# F405__mini_2025-11-19.net
KiCad netlist of a schematic drawn in EasyEDA Pro
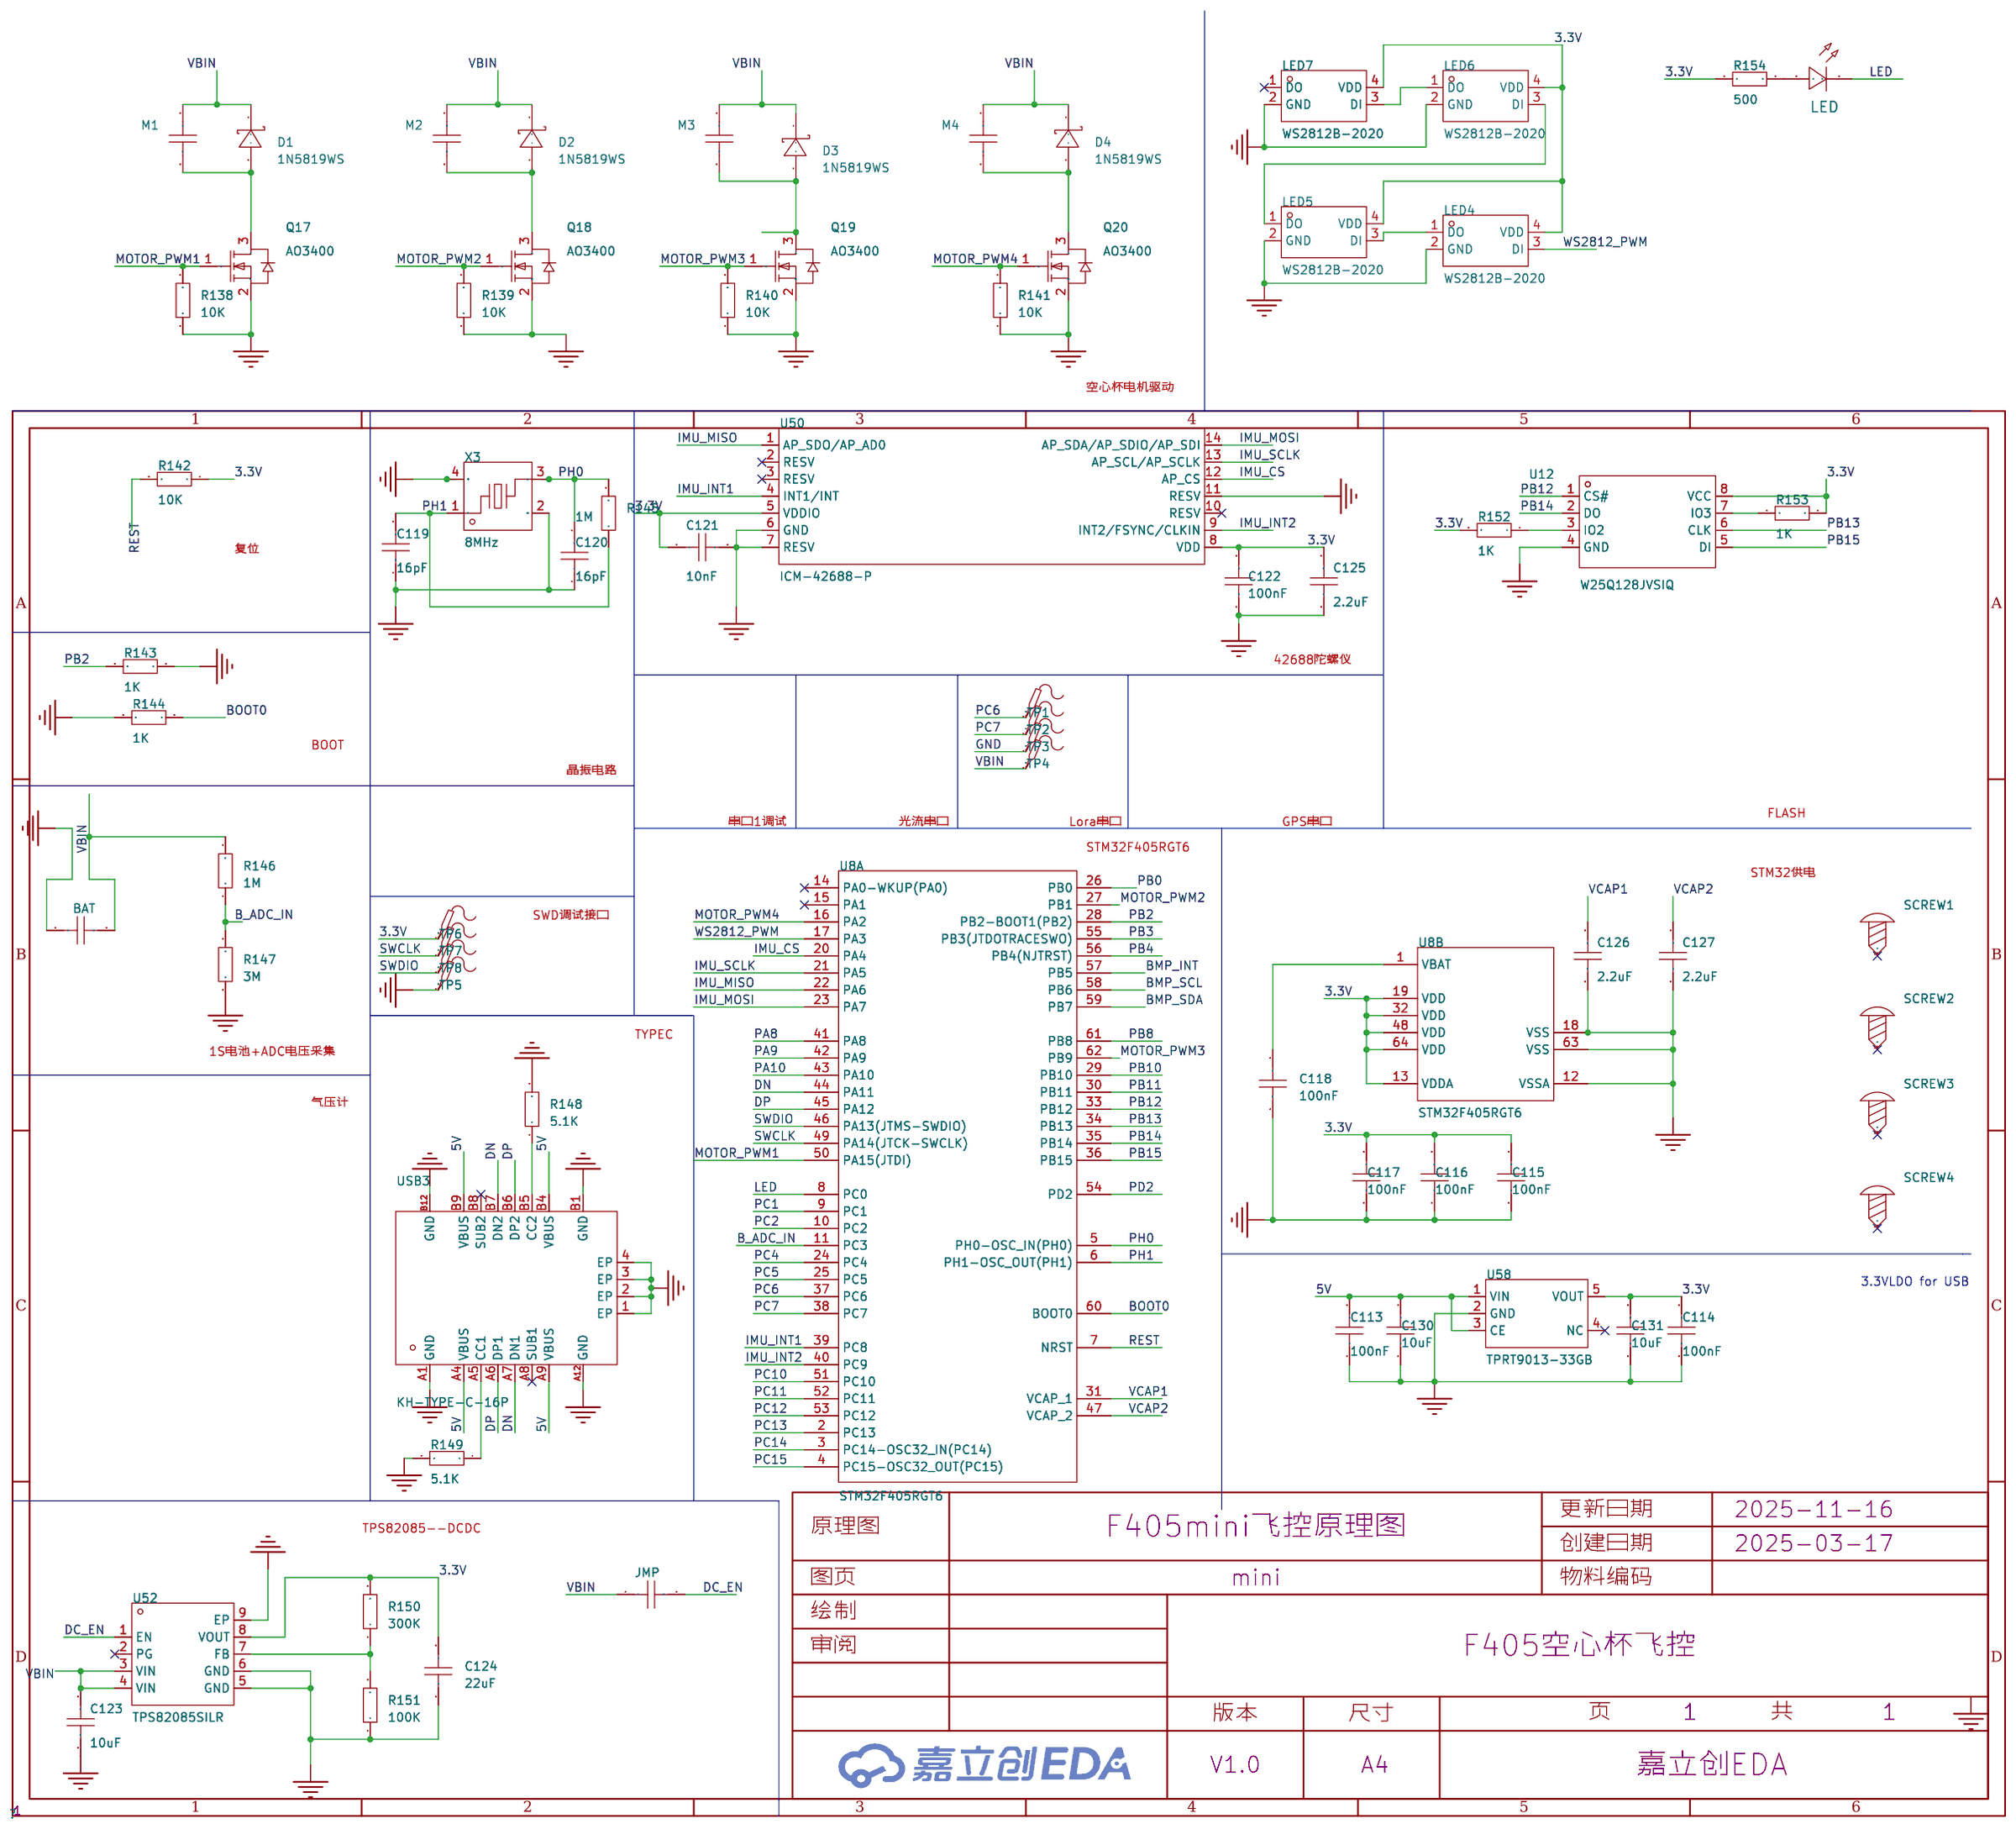
[diagram p0: schematic sheet]

(export (version "E")
  (design (tool "Eeschema 10.0.6"))
  (components
    (comp (ref "BAT")
      (value "3.9nF")
      (footprint "easyedapro:C1812")
      (description "容值:3.9nF;精度:±10%;额定电压:2kV;温度系数:X7R;")
      (fields (field (name "Manufacturer Part") "FV43X392K202EFG") (field (name "Manufacturer") "PSA(信昌电陶)"))
      (libsource (lib "easyedapro") (part "FV43X392K202EFG"))
    )
    (comp (ref "C113")
      (value "100nF")
      (footprint "easyedapro:C1206")
      (libsource (lib "easyedapro") (part "CapAcitance"))
    )
    (comp (ref "C114")
      (value "100nF")
      (footprint "easyedapro:C1206")
      (libsource (lib "easyedapro") (part "CapAcitance"))
    )
    (comp (ref "C115")
      (value "100nF")
      (footprint "easyedapro:C1206")
      (libsource (lib "easyedapro") (part "CapAcitance"))
    )
    (comp (ref "C116")
      (value "100nF")
      (footprint "easyedapro:C1206")
      (libsource (lib "easyedapro") (part "CapAcitance"))
    )
    (comp (ref "C117")
      (value "100nF")
      (footprint "easyedapro:C1206")
      (libsource (lib "easyedapro") (part "CapAcitance"))
    )
    (comp (ref "C118")
      (value "100nF")
      (footprint "easyedapro:C1206")
      (libsource (lib "easyedapro") (part "CapAcitance"))
    )
    (comp (ref "C119")
      (value "16pF")
      (footprint "easyedapro:C1206")
      (libsource (lib "easyedapro") (part "CapAcitance"))
    )
    (comp (ref "C120")
      (value "16pF")
      (footprint "easyedapro:C1206")
      (libsource (lib "easyedapro") (part "CapAcitance"))
    )
    (comp (ref "C121")
      (value "10nF")
      (footprint "easyedapro:C1206")
      (libsource (lib "easyedapro") (part "CapAcitance"))
    )
    (comp (ref "C122")
      (value "100nF")
      (footprint "easyedapro:C1206")
      (libsource (lib "easyedapro") (part "CapAcitance"))
    )
    (comp (ref "C123")
      (value "10uF")
      (footprint "easyedapro:C1206")
      (libsource (lib "easyedapro") (part "CapAcitance"))
    )
    (comp (ref "C124")
      (value "22uF")
      (footprint "easyedapro:C1206")
      (libsource (lib "easyedapro") (part "CapAcitance"))
    )
    (comp (ref "C125")
      (value "2.2uF")
      (footprint "easyedapro:C1206")
      (libsource (lib "easyedapro") (part "CapAcitance"))
    )
    (comp (ref "C126")
      (value "2.2uF")
      (footprint "easyedapro:C1206")
      (libsource (lib "easyedapro") (part "CapAcitance"))
    )
    (comp (ref "C127")
      (value "2.2uF")
      (footprint "easyedapro:C1206")
      (libsource (lib "easyedapro") (part "CapAcitance"))
    )
    (comp (ref "C130")
      (value "10uF")
      (footprint "easyedapro:C1206")
      (libsource (lib "easyedapro") (part "CapAcitance"))
    )
    (comp (ref "C131")
      (value "10uF")
      (footprint "easyedapro:C1206")
      (libsource (lib "easyedapro") (part "CapAcitance"))
    )
    (comp (ref "D1")
      (value "1N5819WS")
      (footprint "easyedapro:SOD-323_L1.8-W1.3-LS2.5-RD")
      (description "正向压降(Vf):600mV@1A;直流反向耐压(Vr):40V;整流电流:1A;")
      (fields (field (name "Manufacturer") "Hottech(合科泰)"))
      (libsource (lib "easyedapro") (part "1N5819WS"))
    )
    (comp (ref "D2")
      (value "1N5819WS")
      (footprint "easyedapro:SOD-323_L1.8-W1.3-LS2.5-RD")
      (description "正向压降(Vf):600mV@1A;直流反向耐压(Vr):40V;整流电流:1A;")
      (fields (field (name "Manufacturer") "Hottech(合科泰)"))
      (libsource (lib "easyedapro") (part "1N5819WS"))
    )
    (comp (ref "D3")
      (value "1N5819WS")
      (footprint "easyedapro:SOD-323_L1.8-W1.3-LS2.5-RD")
      (description "正向压降(Vf):600mV@1A;直流反向耐压(Vr):40V;整流电流:1A;")
      (fields (field (name "Manufacturer") "Hottech(合科泰)"))
      (libsource (lib "easyedapro") (part "1N5819WS"))
    )
    (comp (ref "D4")
      (value "1N5819WS")
      (footprint "easyedapro:SOD-323_L1.8-W1.3-LS2.5-RD")
      (description "正向压降(Vf):600mV@1A;直流反向耐压(Vr):40V;整流电流:1A;")
      (fields (field (name "Manufacturer") "Hottech(合科泰)"))
      (libsource (lib "easyedapro") (part "1N5819WS"))
    )
    (comp (ref "JMP")
      (value "100nF")
      (footprint "easyedapro:C1206")
      (libsource (lib "easyedapro") (part "CapAcitance"))
    )
    (comp (ref "LED")
      (value "~")
      (footprint "easyedapro:LED_0603")
      (libsource (lib "easyedapro") (part "LED_R"))
    )
    (comp (ref "LED4")
      (value "WS2812B-2020")
      (footprint "easyedapro:LED-SMD_4P-L2.0-W2.0-TL_WS2812B-2020")
      (description "12mA，小尺寸，高亮，用于小间距，小尺寸产品（注意防潮，请查阅规格书中对应具体内容）")
      (fields (field (name "Manufacturer") "worldsemi"))
      (libsource (lib "easyedapro") (part "WS2812B-2020"))
    )
    (comp (ref "LED5")
      (value "WS2812B-2020")
      (footprint "easyedapro:LED-SMD_4P-L2.0-W2.0-TL_WS2812B-2020")
      (description "12mA，小尺寸，高亮，用于小间距，小尺寸产品（注意防潮，请查阅规格书中对应具体内容）")
      (fields (field (name "Manufacturer") "worldsemi"))
      (libsource (lib "easyedapro") (part "WS2812B-2020"))
    )
    (comp (ref "LED6")
      (value "WS2812B-2020")
      (footprint "easyedapro:LED-SMD_4P-L2.0-W2.0-TL_WS2812B-2020")
      (description "12mA，小尺寸，高亮，用于小间距，小尺寸产品（注意防潮，请查阅规格书中对应具体内容）")
      (fields (field (name "Manufacturer") "worldsemi"))
      (libsource (lib "easyedapro") (part "WS2812B-2020"))
    )
    (comp (ref "LED7")
      (value "WS2812B-2020")
      (footprint "easyedapro:LED-SMD_4P-L2.0-W2.0-TL_WS2812B-2020")
      (description "12mA，小尺寸，高亮，用于小间距，小尺寸产品（注意防潮，请查阅规格书中对应具体内容）")
      (fields (field (name "Manufacturer") "worldsemi"))
      (libsource (lib "easyedapro") (part "WS2812B-2020"))
    )
    (comp (ref "M1")
      (value "100nF")
      (footprint "easyedapro:C1206")
      (libsource (lib "easyedapro") (part "CapAcitance"))
    )
    (comp (ref "M2")
      (value "100nF")
      (footprint "easyedapro:C1206")
      (libsource (lib "easyedapro") (part "CapAcitance"))
    )
    (comp (ref "M3")
      (value "100nF")
      (footprint "easyedapro:C1206")
      (libsource (lib "easyedapro") (part "CapAcitance"))
    )
    (comp (ref "M4")
      (value "100nF")
      (footprint "easyedapro:C1206")
      (libsource (lib "easyedapro") (part "CapAcitance"))
    )
    (comp (ref "Q17")
      (value "AO3400")
      (footprint "easyedapro:SOT-23_L2.9-W1.3-P1.90-LS2.4-BR")
      (fields (field (name "Manufacturer") "GOODWORK(固得沃克)"))
      (libsource (lib "easyedapro") (part "AO3400_C2938367"))
    )
    (comp (ref "Q18")
      (value "AO3400")
      (footprint "easyedapro:SOT-23_L2.9-W1.3-P1.90-LS2.4-BR")
      (fields (field (name "Manufacturer") "GOODWORK(固得沃克)"))
      (libsource (lib "easyedapro") (part "AO3400_C2938367"))
    )
    (comp (ref "Q19")
      (value "AO3400")
      (footprint "easyedapro:SOT-23_L2.9-W1.3-P1.90-LS2.4-BR")
      (fields (field (name "Manufacturer") "GOODWORK(固得沃克)"))
      (libsource (lib "easyedapro") (part "AO3400_C2938367"))
    )
    (comp (ref "Q20")
      (value "AO3400")
      (footprint "easyedapro:SOT-23_L2.9-W1.3-P1.90-LS2.4-BR")
      (fields (field (name "Manufacturer") "GOODWORK(固得沃克)"))
      (libsource (lib "easyedapro") (part "AO3400_C2938367"))
    )
    (comp (ref "R138")
      (value "10K")
      (footprint "easyedapro:R0402")
      (libsource (lib "easyedapro") (part "电阻"))
    )
    (comp (ref "R139")
      (value "10K")
      (footprint "easyedapro:R0402")
      (libsource (lib "easyedapro") (part "电阻"))
    )
    (comp (ref "R140")
      (value "10K")
      (footprint "easyedapro:R0402")
      (libsource (lib "easyedapro") (part "电阻"))
    )
    (comp (ref "R141")
      (value "10K")
      (footprint "easyedapro:R0402")
      (libsource (lib "easyedapro") (part "电阻"))
    )
    (comp (ref "R142")
      (value "10K")
      (footprint "easyedapro:R0402")
      (libsource (lib "easyedapro") (part "电阻"))
    )
    (comp (ref "R143") (value "1K") (footprint "easyedapro:R0402") (libsource (lib "easyedapro") (part "电阻")))
    (comp (ref "R144") (value "1K") (footprint "easyedapro:R0402") (libsource (lib "easyedapro") (part "电阻")))
    (comp (ref "R145") (value "1M") (footprint "easyedapro:R0402") (libsource (lib "easyedapro") (part "电阻")))
    (comp (ref "R146") (value "1M") (footprint "easyedapro:R0402") (libsource (lib "easyedapro") (part "电阻")))
    (comp (ref "R147") (value "3M") (footprint "easyedapro:R0402") (libsource (lib "easyedapro") (part "电阻")))
    (comp (ref "R148")
      (value "5.1K")
      (footprint "easyedapro:R0402")
      (libsource (lib "easyedapro") (part "电阻"))
    )
    (comp (ref "R149")
      (value "5.1K")
      (footprint "easyedapro:R0402")
      (libsource (lib "easyedapro") (part "电阻"))
    )
    (comp (ref "R150")
      (value "300K")
      (footprint "easyedapro:R0402")
      (libsource (lib "easyedapro") (part "电阻"))
    )
    (comp (ref "R151")
      (value "100K")
      (footprint "easyedapro:R0402")
      (libsource (lib "easyedapro") (part "电阻"))
    )
    (comp (ref "R152") (value "1K") (footprint "easyedapro:R0402") (libsource (lib "easyedapro") (part "电阻")))
    (comp (ref "R153") (value "1K") (footprint "easyedapro:R0402") (libsource (lib "easyedapro") (part "电阻")))
    (comp (ref "R154")
      (value "500")
      (footprint "easyedapro:R0402")
      (libsource (lib "easyedapro") (part "电阻"))
    )
    (comp (ref "SCREW1")
      (value "~")
      (footprint "easyedapro:M2螺丝")
      (libsource (lib "easyedapro") (part "螺丝孔"))
    )
    (comp (ref "SCREW2")
      (value "~")
      (footprint "easyedapro:M2螺丝")
      (libsource (lib "easyedapro") (part "螺丝孔"))
    )
    (comp (ref "SCREW3")
      (value "~")
      (footprint "easyedapro:M2螺丝")
      (libsource (lib "easyedapro") (part "螺丝孔"))
    )
    (comp (ref "SCREW4")
      (value "~")
      (footprint "easyedapro:M2螺丝")
      (libsource (lib "easyedapro") (part "螺丝孔"))
    )
    (comp (ref "TP1")
      (value "~")
      (footprint "easyedapro:Test-Point-0.5mm")
      (description "Test Point 测试点")
      (libsource (lib "easyedapro") (part "Test-Point"))
    )
    (comp (ref "TP2")
      (value "~")
      (footprint "easyedapro:Test-Point-0.5mm")
      (description "Test Point 测试点")
      (libsource (lib "easyedapro") (part "Test-Point"))
    )
    (comp (ref "TP3")
      (value "~")
      (footprint "easyedapro:Test-Point-0.5mm")
      (description "Test Point 测试点")
      (libsource (lib "easyedapro") (part "Test-Point"))
    )
    (comp (ref "TP4")
      (value "~")
      (footprint "easyedapro:Test-Point-0.5mm")
      (description "Test Point 测试点")
      (libsource (lib "easyedapro") (part "Test-Point"))
    )
    (comp (ref "TP5")
      (value "~")
      (footprint "easyedapro:Test-Point-0.5mm")
      (description "Test Point 测试点")
      (libsource (lib "easyedapro") (part "Test-Point"))
    )
    (comp (ref "TP6")
      (value "~")
      (footprint "easyedapro:Test-Point-0.5mm")
      (description "Test Point 测试点")
      (libsource (lib "easyedapro") (part "Test-Point"))
    )
    (comp (ref "TP7")
      (value "~")
      (footprint "easyedapro:Test-Point-0.5mm")
      (description "Test Point 测试点")
      (libsource (lib "easyedapro") (part "Test-Point"))
    )
    (comp (ref "TP8")
      (value "~")
      (footprint "easyedapro:Test-Point-0.5mm")
      (description "Test Point 测试点")
      (libsource (lib "easyedapro") (part "Test-Point"))
    )
    (comp (ref "U8")
      (value "STM32F405RGT6")
      (footprint "easyedapro:LQFP-64_L10.0-W10.0-P0.50-LS12.0-BL")
      (description "CPU内核:ARM-M4;程序存储容量:1MB;RAM总容量:192KB;GPIO端口数量:51;工作电压范围:1.8V~3.6V;CPU最大主频:168MHz;程序存储器类型:FLASH;")
      (fields (field (name "Manufacturer") "ST(意法半导体)"))
      (libsource (lib "easyedapro") (part "STM32F405RGT6"))
    )
    (comp (ref "U12")
      (value "W25Q128JVSIQ")
      (footprint "easyedapro:SOIC-8_L5.3-W5.3-P1.27-LS8.0-BL")
      (description "接口类型:-;存储容量:128Mbit;时钟频率(fc):-;")
      (fields (field (name "Manufacturer") "WINBOND(华邦)"))
      (libsource (lib "easyedapro") (part "w25q128jvsiqtr"))
    )
    (comp (ref "U50")
      (value "ICM-42688-P")
      (footprint "easyedapro:LGA-14_L3.0-W2.5-P0.50-TL")
      (description "传感器类型:加速度计陀螺仪;")
      (fields (field (name "Manufacturer") "TDK InvenSense(应美盛)"))
      (libsource (lib "easyedapro") (part "ICM-42688-P"))
    )
    (comp (ref "U52")
      (value "TPS82085SILR")
      (footprint "easyedapro:USIP-8_L3.0-W2.8-P0.65-BL-EP")
      (description "TPS82085 集成感应器的 3A 降压转换器（截面 &lt; 1.3mm）")
      (fields (field (name "Manufacturer") "TI(德州仪器)"))
      (libsource (lib "easyedapro") (part "TPS82085SILR"))
    )
    (comp (ref "U58")
      (value "TPRT9013-33GB")
      (footprint "easyedapro:SOT-23-5_L3.0-W1.7-P0.95-LS2.8-BL")
      (description "输出类型:固定;工作电压:7V;输出电压:3.3V;输出电流:500mA;电源纹波抑制比(PSRR):70dB@(1kHz);输出极性:正极;")
      (fields (field (name "Manufacturer") "TECH PUBLIC(台舟)"))
      (libsource (lib "easyedapro") (part "TPRT9013-33GB"))
    )
    (comp (ref "USB3")
      (value "KH-TYPE-C-16P")
      (footprint "easyedapro:USB-C-SMD_KH-TYPE-C-16P")
      (description "连接器类型:Type-C;标准:-;公母:母;端口数量:1;触点数量:16P;安装方式:卧贴;额定电流 - 电源:3A;工作温度范围:-40°C~+85°C;")
      (fields (field (name "Manufacturer") "kinghelm(金航标)"))
      (libsource (lib "easyedapro") (part "KH-TYPE-C-16P"))
    )
    (comp (ref "X3")
      (value "8MHz")
      (footprint "easyedapro:CRYSTAL-SMD_4P-L3.2-W2.5-BL")
      (description "晶振类型:贴片晶振;频率:8MHz;常温频差:±10ppm;外接负载电容:20pF;频率稳定度(全温):±20ppm;")
      (fields (field (name "Manufacturer Part") "X32258MSB4SI") (field (name "Manufacturer") "YXC(扬兴晶振)"))
      (libsource (lib "easyedapro") (part "X32258MSB4SI"))
    )
  )
  (nets
    (net (code "1") (name "/3.3V") (class "Default")
      (node (ref "C114") (pin "2") (pinfunction "2_2") (pintype "input"))
      (node (ref "C115") (pin "2") (pinfunction "2_2") (pintype "input"))
      (node (ref "C116") (pin "2") (pinfunction "2_2") (pintype "input"))
      (node (ref "C117") (pin "2") (pinfunction "2_2") (pintype "input"))
      (node (ref "C121") (pin "1") (pinfunction "1_1") (pintype "input"))
      (node (ref "C122") (pin "2") (pinfunction "2_2") (pintype "input"))
      (node (ref "C124") (pin "2") (pinfunction "2_2") (pintype "input"))
      (node (ref "C125") (pin "2") (pinfunction "2_2") (pintype "input"))
      (node (ref "C131") (pin "2") (pinfunction "2_2") (pintype "input"))
      (node (ref "LED4") (pin "4") (pinfunction "VDD_4") (pintype "unspecified"))
      (node (ref "LED5") (pin "4") (pinfunction "VDD_4") (pintype "unspecified"))
      (node (ref "LED6") (pin "4") (pinfunction "VDD_4") (pintype "unspecified"))
      (node (ref "LED7") (pin "4") (pinfunction "VDD_4") (pintype "unspecified"))
      (node (ref "R142") (pin "1") (pinfunction "1_1") (pintype "input"))
      (node (ref "R150") (pin "2") (pinfunction "2_2") (pintype "input"))
      (node (ref "R152") (pin "2") (pinfunction "2_2") (pintype "input"))
      (node (ref "R153") (pin "1") (pinfunction "1_1") (pintype "input"))
      (node (ref "R154") (pin "1") (pinfunction "1_1") (pintype "input"))
      (node (ref "TP6") (pin "1") (pinfunction "1_1") (pintype "input"))
      (node (ref "U12") (pin "8") (pinfunction "VCC_8") (pintype "unspecified"))
      (node (ref "U50") (pin "5") (pinfunction "VDDIO_5") (pintype "unspecified"))
      (node (ref "U50") (pin "8") (pinfunction "VDD_8") (pintype "unspecified"))
      (node (ref "U52") (pin "8") (pinfunction "VOUT_8") (pintype "unspecified"))
      (node (ref "U58") (pin "5") (pinfunction "VOUT_5") (pintype "unspecified"))
      (node (ref "U8") (pin "13") (pinfunction "VDDA_13") (pintype "unspecified"))
      (node (ref "U8") (pin "19") (pinfunction "VDD_19") (pintype "unspecified"))
      (node (ref "U8") (pin "32") (pinfunction "VDD_32") (pintype "unspecified"))
      (node (ref "U8") (pin "48") (pinfunction "VDD_48") (pintype "unspecified"))
      (node (ref "U8") (pin "64") (pinfunction "VDD_64") (pintype "unspecified"))
    )
    (net (code "2") (name "/5V") (class "Default")
      (node (ref "C113") (pin "2") (pinfunction "2_2") (pintype "input"))
      (node (ref "C130") (pin "2") (pinfunction "2_2") (pintype "input"))
      (node (ref "U58") (pin "1") (pinfunction "VIN_1") (pintype "unspecified"))
      (node (ref "U58") (pin "3") (pinfunction "CE_3") (pintype "unspecified"))
      (node (ref "USB3") (pin "A4") (pinfunction "VBUS_A4") (pintype "unspecified"))
      (node (ref "USB3") (pin "A9") (pinfunction "VBUS_A9") (pintype "unspecified"))
      (node (ref "USB3") (pin "B4") (pinfunction "VBUS_B4") (pintype "unspecified"))
      (node (ref "USB3") (pin "B9") (pinfunction "VBUS_B9") (pintype "unspecified"))
    )
    (net (code "3") (name "/BMP_INT") (class "Default")
      (node (ref "U8") (pin "57") (pinfunction "PB5_57") (pintype "bidirectional"))
    )
    (net (code "4") (name "/BMP_SCL") (class "Default")
      (node (ref "U8") (pin "58") (pinfunction "PB6_58") (pintype "bidirectional"))
    )
    (net (code "5") (name "/BMP_SDA") (class "Default")
      (node (ref "U8") (pin "59") (pinfunction "PB7_59") (pintype "bidirectional"))
    )
    (net (code "6") (name "/BOOT0") (class "Default")
      (node (ref "R144") (pin "1") (pinfunction "1_1") (pintype "input"))
      (node (ref "U8") (pin "60") (pinfunction "BOOT0_60") (pintype "unspecified"))
    )
    (net (code "7") (name "/B_ADC_IN") (class "Default")
      (node (ref "R146") (pin "1") (pinfunction "1_1") (pintype "input"))
      (node (ref "R147") (pin "2") (pinfunction "2_2") (pintype "input"))
      (node (ref "U8") (pin "11") (pinfunction "PC3_11") (pintype "bidirectional"))
    )
    (net (code "8") (name "/DC_EN") (class "Default")
      (node (ref "JMP") (pin "2") (pinfunction "2_2") (pintype "input"))
      (node (ref "U52") (pin "1") (pinfunction "EN_1") (pintype "unspecified"))
    )
    (net (code "9") (name "/DN") (class "Default")
      (node (ref "U8") (pin "44") (pinfunction "PA11_44") (pintype "bidirectional"))
      (node (ref "USB3") (pin "A7") (pinfunction "DN1_A7") (pintype "unspecified"))
      (node (ref "USB3") (pin "B7") (pinfunction "DN2_B7") (pintype "unspecified"))
    )
    (net (code "10") (name "/DP") (class "Default")
      (node (ref "U8") (pin "45") (pinfunction "PA12_45") (pintype "bidirectional"))
      (node (ref "USB3") (pin "A6") (pinfunction "DP1_A6") (pintype "unspecified"))
      (node (ref "USB3") (pin "B6") (pinfunction "DP2_B6") (pintype "unspecified"))
    )
    (net (code "11") (name "/IMU_CS") (class "Default")
      (node (ref "U50") (pin "12") (pinfunction "AP_CS_12") (pintype "unspecified"))
      (node (ref "U8") (pin "20") (pinfunction "PA4_20") (pintype "bidirectional"))
    )
    (net (code "12") (name "/IMU_INT1") (class "Default")
      (node (ref "U50") (pin "4") (pinfunction "INT1/INT_4") (pintype "unspecified"))
      (node (ref "U8") (pin "39") (pinfunction "PC8_39") (pintype "bidirectional"))
    )
    (net (code "13") (name "/IMU_INT2") (class "Default")
      (node (ref "U50") (pin "9") (pinfunction "INT2/FSYNC/CLKIN_9") (pintype "unspecified"))
      (node (ref "U8") (pin "40") (pinfunction "PC9_40") (pintype "bidirectional"))
    )
    (net (code "14") (name "/IMU_MISO") (class "Default")
      (node (ref "U50") (pin "1") (pinfunction "AP_SDO/AP_AD0_1") (pintype "unspecified"))
      (node (ref "U8") (pin "22") (pinfunction "PA6_22") (pintype "bidirectional"))
    )
    (net (code "15") (name "/IMU_MOSI") (class "Default")
      (node (ref "U50") (pin "14") (pinfunction "AP_SDA/AP_SDIO/AP_SDI_14") (pintype "unspecified"))
      (node (ref "U8") (pin "23") (pinfunction "PA7_23") (pintype "bidirectional"))
    )
    (net (code "16") (name "/IMU_SCLK") (class "Default")
      (node (ref "U50") (pin "13") (pinfunction "AP_SCL/AP_SCLK_13") (pintype "unspecified"))
      (node (ref "U8") (pin "21") (pinfunction "PA5_21") (pintype "bidirectional"))
    )
    (net (code "17") (name "/LED") (class "Default")
      (node (ref "LED") (pin "1") (pinfunction "C_1") (pintype "input"))
      (node (ref "U8") (pin "8") (pinfunction "PC0_8") (pintype "bidirectional"))
    )
    (net (code "18") (name "/MOTOR_PWM1") (class "Default")
      (node (ref "Q17") (pin "1") (pinfunction "G_1") (pintype "unspecified"))
      (node (ref "R138") (pin "2") (pinfunction "2_2") (pintype "input"))
      (node (ref "U8") (pin "50") (pinfunction "PA15(JTDI)_50") (pintype "bidirectional"))
    )
    (net (code "19") (name "/MOTOR_PWM2") (class "Default")
      (node (ref "Q18") (pin "1") (pinfunction "G_1") (pintype "unspecified"))
      (node (ref "R139") (pin "2") (pinfunction "2_2") (pintype "input"))
      (node (ref "U8") (pin "27") (pinfunction "PB1_27") (pintype "bidirectional"))
    )
    (net (code "20") (name "/MOTOR_PWM3") (class "Default")
      (node (ref "Q19") (pin "1") (pinfunction "G_1") (pintype "unspecified"))
      (node (ref "R140") (pin "2") (pinfunction "2_2") (pintype "input"))
      (node (ref "U8") (pin "62") (pinfunction "PB9_62") (pintype "bidirectional"))
    )
    (net (code "21") (name "/MOTOR_PWM4") (class "Default")
      (node (ref "Q20") (pin "1") (pinfunction "G_1") (pintype "unspecified"))
      (node (ref "R141") (pin "2") (pinfunction "2_2") (pintype "input"))
      (node (ref "U8") (pin "16") (pinfunction "PA2_16") (pintype "bidirectional"))
    )
    (net (code "22") (name "/PA8") (class "Default")
      (node (ref "U8") (pin "41") (pinfunction "PA8_41") (pintype "bidirectional"))
    )
    (net (code "23") (name "/PA9") (class "Default")
      (node (ref "U8") (pin "42") (pinfunction "PA9_42") (pintype "bidirectional"))
    )
    (net (code "24") (name "/PA10") (class "Default")
      (node (ref "U8") (pin "43") (pinfunction "PA10_43") (pintype "bidirectional"))
    )
    (net (code "25") (name "/PB0") (class "Default")
      (node (ref "U8") (pin "26") (pinfunction "PB0_26") (pintype "bidirectional"))
    )
    (net (code "26") (name "/PB2") (class "Default")
      (node (ref "R143") (pin "2") (pinfunction "2_2") (pintype "input"))
      (node (ref "U8") (pin "28") (pinfunction "PB2-BOOT1(PB2)_28") (pintype "bidirectional"))
    )
    (net (code "27") (name "/PB3") (class "Default")
      (node (ref "U8") (pin "55") (pinfunction "PB3(JTDOTRACESWO)_55") (pintype "bidirectional"))
    )
    (net (code "28") (name "/PB4") (class "Default")
      (node (ref "U8") (pin "56") (pinfunction "PB4(NJTRST)_56") (pintype "bidirectional"))
    )
    (net (code "29") (name "/PB8") (class "Default")
      (node (ref "U8") (pin "61") (pinfunction "PB8_61") (pintype "bidirectional"))
    )
    (net (code "30") (name "/PB10") (class "Default")
      (node (ref "U8") (pin "29") (pinfunction "PB10_29") (pintype "bidirectional"))
    )
    (net (code "31") (name "/PB11") (class "Default")
      (node (ref "U8") (pin "30") (pinfunction "PB11_30") (pintype "bidirectional"))
    )
    (net (code "32") (name "/PB12") (class "Default")
      (node (ref "U12") (pin "1") (pinfunction "CS#_1") (pintype "unspecified"))
      (node (ref "U8") (pin "33") (pinfunction "PB12_33") (pintype "bidirectional"))
    )
    (net (code "33") (name "/PB13") (class "Default")
      (node (ref "U12") (pin "6") (pinfunction "CLK_6") (pintype "unspecified"))
      (node (ref "U8") (pin "34") (pinfunction "PB13_34") (pintype "bidirectional"))
    )
    (net (code "34") (name "/PB14") (class "Default")
      (node (ref "U12") (pin "2") (pinfunction "DO_2") (pintype "unspecified"))
      (node (ref "U8") (pin "35") (pinfunction "PB14_35") (pintype "bidirectional"))
    )
    (net (code "35") (name "/PB15") (class "Default")
      (node (ref "U12") (pin "5") (pinfunction "DI_5") (pintype "unspecified"))
      (node (ref "U8") (pin "36") (pinfunction "PB15_36") (pintype "bidirectional"))
    )
    (net (code "36") (name "/PC1") (class "Default")
      (node (ref "U8") (pin "9") (pinfunction "PC1_9") (pintype "bidirectional"))
    )
    (net (code "37") (name "/PC2") (class "Default")
      (node (ref "U8") (pin "10") (pinfunction "PC2_10") (pintype "bidirectional"))
    )
    (net (code "38") (name "/PC4") (class "Default")
      (node (ref "U8") (pin "24") (pinfunction "PC4_24") (pintype "bidirectional"))
    )
    (net (code "39") (name "/PC5") (class "Default")
      (node (ref "U8") (pin "25") (pinfunction "PC5_25") (pintype "bidirectional"))
    )
    (net (code "40") (name "/PC6") (class "Default")
      (node (ref "TP1") (pin "1") (pinfunction "1_1") (pintype "input"))
      (node (ref "U8") (pin "37") (pinfunction "PC6_37") (pintype "bidirectional"))
    )
    (net (code "41") (name "/PC7") (class "Default")
      (node (ref "TP2") (pin "1") (pinfunction "1_1") (pintype "input"))
      (node (ref "U8") (pin "38") (pinfunction "PC7_38") (pintype "bidirectional"))
    )
    (net (code "42") (name "/PC10") (class "Default")
      (node (ref "U8") (pin "51") (pinfunction "PC10_51") (pintype "bidirectional"))
    )
    (net (code "43") (name "/PC11") (class "Default")
      (node (ref "U8") (pin "52") (pinfunction "PC11_52") (pintype "bidirectional"))
    )
    (net (code "44") (name "/PC12") (class "Default")
      (node (ref "U8") (pin "53") (pinfunction "PC12_53") (pintype "bidirectional"))
    )
    (net (code "45") (name "/PC13") (class "Default")
      (node (ref "U8") (pin "2") (pinfunction "PC13_2") (pintype "bidirectional"))
    )
    (net (code "46") (name "/PC14") (class "Default")
      (node (ref "U8") (pin "3") (pinfunction "PC14-OSC32_IN(PC14)_3") (pintype "bidirectional"))
    )
    (net (code "47") (name "/PC15") (class "Default")
      (node (ref "U8") (pin "4") (pinfunction "PC15-OSC32_OUT(PC15)_4") (pintype "bidirectional"))
    )
    (net (code "48") (name "/PD2") (class "Default")
      (node (ref "U8") (pin "54") (pinfunction "PD2_54") (pintype "bidirectional"))
    )
    (net (code "49") (name "/PH0") (class "Default")
      (node (ref "C120") (pin "2") (pinfunction "2_2") (pintype "input"))
      (node (ref "R145") (pin "2") (pinfunction "2_2") (pintype "input"))
      (node (ref "U8") (pin "5") (pinfunction "PH0-OSC_IN(PH0)_5") (pintype "bidirectional"))
      (node (ref "X3") (pin "3") (pinfunction "3_3") (pintype "input"))
    )
    (net (code "50") (name "/PH1") (class "Default")
      (node (ref "C119") (pin "2") (pinfunction "2_2") (pintype "input"))
      (node (ref "R145") (pin "1") (pinfunction "1_1") (pintype "input"))
      (node (ref "U8") (pin "6") (pinfunction "PH1-OSC_OUT(PH1)_6") (pintype "bidirectional"))
      (node (ref "X3") (pin "1") (pinfunction "1_1") (pintype "input"))
    )
    (net (code "51") (name "/REST") (class "Default")
      (node (ref "R142") (pin "2") (pinfunction "2_2") (pintype "input"))
      (node (ref "U8") (pin "7") (pinfunction "NRST_7") (pintype "bidirectional"))
    )
    (net (code "52") (name "/SWCLK") (class "Default")
      (node (ref "TP7") (pin "1") (pinfunction "1_1") (pintype "input"))
      (node (ref "U8") (pin "49") (pinfunction "PA14(JTCK-SWCLK)_49") (pintype "bidirectional"))
    )
    (net (code "53") (name "/SWDIO") (class "Default")
      (node (ref "TP8") (pin "1") (pinfunction "1_1") (pintype "input"))
      (node (ref "U8") (pin "46") (pinfunction "PA13(JTMS-SWDIO)_46") (pintype "bidirectional"))
    )
    (net (code "54") (name "/VBIN") (class "Default")
      (node (ref "BAT") (pin "2") (pinfunction "2_2") (pintype "unspecified"))
      (node (ref "C123") (pin "2") (pinfunction "2_2") (pintype "input"))
      (node (ref "D1") (pin "1") (pinfunction "K_1") (pintype "unspecified"))
      (node (ref "D2") (pin "1") (pinfunction "K_1") (pintype "unspecified"))
      (node (ref "D3") (pin "1") (pinfunction "K_1") (pintype "unspecified"))
      (node (ref "D4") (pin "1") (pinfunction "K_1") (pintype "unspecified"))
      (node (ref "JMP") (pin "1") (pinfunction "1_1") (pintype "input"))
      (node (ref "M1") (pin "1") (pinfunction "1_1") (pintype "input"))
      (node (ref "M2") (pin "1") (pinfunction "1_1") (pintype "input"))
      (node (ref "M3") (pin "1") (pinfunction "1_1") (pintype "input"))
      (node (ref "M4") (pin "1") (pinfunction "1_1") (pintype "input"))
      (node (ref "R146") (pin "2") (pinfunction "2_2") (pintype "input"))
      (node (ref "TP4") (pin "1") (pinfunction "1_1") (pintype "input"))
      (node (ref "U52") (pin "3") (pinfunction "VIN_3") (pintype "unspecified"))
      (node (ref "U52") (pin "4") (pinfunction "VIN_4") (pintype "unspecified"))
    )
    (net (code "55") (name "/VCAP1") (class "Default")
      (node (ref "C126") (pin "2") (pinfunction "2_2") (pintype "input"))
      (node (ref "U8") (pin "31") (pinfunction "VCAP_1_31") (pintype "unspecified"))
    )
    (net (code "56") (name "/VCAP2") (class "Default")
      (node (ref "C127") (pin "2") (pinfunction "2_2") (pintype "input"))
      (node (ref "U8") (pin "47") (pinfunction "VCAP_2_47") (pintype "unspecified"))
    )
    (net (code "57") (name "/WS2812_PWM") (class "Default")
      (node (ref "LED4") (pin "3") (pinfunction "DI_3") (pintype "unspecified"))
      (node (ref "U8") (pin "17") (pinfunction "PA3_17") (pintype "bidirectional"))
    )
    (net (code "58") (name "GND") (class "Default")
      (node (ref "BAT") (pin "1") (pinfunction "1_1") (pintype "unspecified"))
      (node (ref "C113") (pin "1") (pinfunction "1_1") (pintype "input"))
      (node (ref "C114") (pin "1") (pinfunction "1_1") (pintype "input"))
      (node (ref "C115") (pin "1") (pinfunction "1_1") (pintype "input"))
      (node (ref "C116") (pin "1") (pinfunction "1_1") (pintype "input"))
      (node (ref "C117") (pin "1") (pinfunction "1_1") (pintype "input"))
      (node (ref "C118") (pin "1") (pinfunction "1_1") (pintype "input"))
      (node (ref "C119") (pin "1") (pinfunction "1_1") (pintype "input"))
      (node (ref "C120") (pin "1") (pinfunction "1_1") (pintype "input"))
      (node (ref "C121") (pin "2") (pinfunction "2_2") (pintype "input"))
      (node (ref "C122") (pin "1") (pinfunction "1_1") (pintype "input"))
      (node (ref "C123") (pin "1") (pinfunction "1_1") (pintype "input"))
      (node (ref "C124") (pin "1") (pinfunction "1_1") (pintype "input"))
      (node (ref "C125") (pin "1") (pinfunction "1_1") (pintype "input"))
      (node (ref "C126") (pin "1") (pinfunction "1_1") (pintype "input"))
      (node (ref "C127") (pin "1") (pinfunction "1_1") (pintype "input"))
      (node (ref "C130") (pin "1") (pinfunction "1_1") (pintype "input"))
      (node (ref "C131") (pin "1") (pinfunction "1_1") (pintype "input"))
      (node (ref "LED4") (pin "2") (pinfunction "GND_2") (pintype "unspecified"))
      (node (ref "LED5") (pin "2") (pinfunction "GND_2") (pintype "unspecified"))
      (node (ref "LED6") (pin "2") (pinfunction "GND_2") (pintype "unspecified"))
      (node (ref "LED7") (pin "2") (pinfunction "GND_2") (pintype "unspecified"))
      (node (ref "Q17") (pin "2") (pinfunction "S_2") (pintype "unspecified"))
      (node (ref "Q18") (pin "2") (pinfunction "S_2") (pintype "unspecified"))
      (node (ref "Q19") (pin "2") (pinfunction "S_2") (pintype "unspecified"))
      (node (ref "Q20") (pin "2") (pinfunction "S_2") (pintype "unspecified"))
      (node (ref "R138") (pin "1") (pinfunction "1_1") (pintype "input"))
      (node (ref "R139") (pin "1") (pinfunction "1_1") (pintype "input"))
      (node (ref "R140") (pin "1") (pinfunction "1_1") (pintype "input"))
      (node (ref "R141") (pin "1") (pinfunction "1_1") (pintype "input"))
      (node (ref "R143") (pin "1") (pinfunction "1_1") (pintype "input"))
      (node (ref "R144") (pin "2") (pinfunction "2_2") (pintype "input"))
      (node (ref "R147") (pin "1") (pinfunction "1_1") (pintype "input"))
      (node (ref "R148") (pin "2") (pinfunction "2_2") (pintype "input"))
      (node (ref "R149") (pin "2") (pinfunction "2_2") (pintype "input"))
      (node (ref "R151") (pin "1") (pinfunction "1_1") (pintype "input"))
      (node (ref "TP3") (pin "1") (pinfunction "1_1") (pintype "input"))
      (node (ref "TP5") (pin "1") (pinfunction "1_1") (pintype "input"))
      (node (ref "U12") (pin "4") (pinfunction "GND_4") (pintype "unspecified"))
      (node (ref "U50") (pin "11") (pinfunction "RESV_11") (pintype "unspecified"))
      (node (ref "U50") (pin "6") (pinfunction "GND_6") (pintype "unspecified"))
      (node (ref "U50") (pin "7") (pinfunction "RESV_7") (pintype "unspecified"))
      (node (ref "U52") (pin "5") (pinfunction "GND_5") (pintype "unspecified"))
      (node (ref "U52") (pin "6") (pinfunction "GND_6") (pintype "unspecified"))
      (node (ref "U52") (pin "9") (pinfunction "EP_9") (pintype "unspecified"))
      (node (ref "U58") (pin "2") (pinfunction "GND_2") (pintype "unspecified"))
      (node (ref "U8") (pin "12") (pinfunction "VSSA_12") (pintype "unspecified"))
      (node (ref "U8") (pin "18") (pinfunction "VSS_18") (pintype "unspecified"))
      (node (ref "U8") (pin "63") (pinfunction "VSS_63") (pintype "unspecified"))
      (node (ref "USB3") (pin "1") (pinfunction "EP_1") (pintype "unspecified"))
      (node (ref "USB3") (pin "2") (pinfunction "EP_2") (pintype "unspecified"))
      (node (ref "USB3") (pin "3") (pinfunction "EP_3") (pintype "unspecified"))
      (node (ref "USB3") (pin "4") (pinfunction "EP_4") (pintype "unspecified"))
      (node (ref "USB3") (pin "A1") (pinfunction "GND_A1") (pintype "unspecified"))
      (node (ref "USB3") (pin "A12") (pinfunction "GND_A12") (pintype "unspecified"))
      (node (ref "USB3") (pin "B1") (pinfunction "GND_B1") (pintype "unspecified"))
      (node (ref "USB3") (pin "B12") (pinfunction "GND_B12") (pintype "unspecified"))
      (node (ref "X3") (pin "2") (pinfunction "GND_2") (pintype "input"))
      (node (ref "X3") (pin "4") (pinfunction "GND_4") (pintype "input"))
    )
    (net (code "59") (name "Net-(D1-A)") (class "Default")
      (node (ref "D1") (pin "2") (pinfunction "A_2") (pintype "unspecified"))
      (node (ref "M1") (pin "2") (pinfunction "2_2") (pintype "input"))
      (node (ref "Q17") (pin "3") (pinfunction "D_3") (pintype "unspecified"))
    )
    (net (code "60") (name "Net-(D2-A)") (class "Default")
      (node (ref "D2") (pin "2") (pinfunction "A_2") (pintype "unspecified"))
      (node (ref "M2") (pin "2") (pinfunction "2_2") (pintype "input"))
      (node (ref "Q18") (pin "3") (pinfunction "D_3") (pintype "unspecified"))
    )
    (net (code "61") (name "Net-(D3-A)") (class "Default")
      (node (ref "D3") (pin "2") (pinfunction "A_2") (pintype "unspecified"))
      (node (ref "M3") (pin "2") (pinfunction "2_2") (pintype "input"))
      (node (ref "Q19") (pin "3") (pinfunction "D_3") (pintype "unspecified"))
    )
    (net (code "62") (name "Net-(D4-A)") (class "Default")
      (node (ref "D4") (pin "2") (pinfunction "A_2") (pintype "unspecified"))
      (node (ref "M4") (pin "2") (pinfunction "2_2") (pintype "input"))
      (node (ref "Q20") (pin "3") (pinfunction "D_3") (pintype "unspecified"))
    )
    (net (code "63") (name "Net-(LED-A)") (class "Default")
      (node (ref "LED") (pin "2") (pinfunction "A_2") (pintype "input"))
      (node (ref "R154") (pin "2") (pinfunction "2_2") (pintype "input"))
    )
    (net (code "64") (name "Net-(LED4-DO)") (class "Default")
      (node (ref "LED4") (pin "1") (pinfunction "DO_1") (pintype "unspecified"))
      (node (ref "LED5") (pin "3") (pinfunction "DI_3") (pintype "unspecified"))
    )
    (net (code "65") (name "Net-(LED5-DO)") (class "Default")
      (node (ref "LED5") (pin "1") (pinfunction "DO_1") (pintype "unspecified"))
      (node (ref "LED6") (pin "3") (pinfunction "DI_3") (pintype "unspecified"))
    )
    (net (code "66") (name "Net-(LED6-DO)") (class "Default")
      (node (ref "LED6") (pin "1") (pinfunction "DO_1") (pintype "unspecified"))
      (node (ref "LED7") (pin "3") (pinfunction "DI_3") (pintype "unspecified"))
    )
    (net (code "67") (name "Net-(U8B-VBAT)") (class "Default")
      (node (ref "C118") (pin "2") (pinfunction "2_2") (pintype "input"))
      (node (ref "U8") (pin "1") (pinfunction "VBAT_1") (pintype "unspecified"))
    )
    (net (code "68") (name "Net-(U12-IO2)") (class "Default")
      (node (ref "R152") (pin "1") (pinfunction "1_1") (pintype "input"))
      (node (ref "U12") (pin "3") (pinfunction "IO2_3") (pintype "unspecified"))
    )
    (net (code "69") (name "Net-(U12-IO3)") (class "Default")
      (node (ref "R153") (pin "2") (pinfunction "2_2") (pintype "input"))
      (node (ref "U12") (pin "7") (pinfunction "IO3_7") (pintype "unspecified"))
    )
    (net (code "70") (name "Net-(U52-FB)") (class "Default")
      (node (ref "R150") (pin "1") (pinfunction "1_1") (pintype "input"))
      (node (ref "R151") (pin "2") (pinfunction "2_2") (pintype "input"))
      (node (ref "U52") (pin "7") (pinfunction "FB_7") (pintype "unspecified"))
    )
    (net (code "71") (name "Net-(USB3-CC1)") (class "Default")
      (node (ref "R149") (pin "1") (pinfunction "1_1") (pintype "input"))
      (node (ref "USB3") (pin "A5") (pinfunction "CC1_A5") (pintype "unspecified"))
    )
    (net (code "72") (name "Net-(USB3-CC2)") (class "Default")
      (node (ref "R148") (pin "1") (pinfunction "1_1") (pintype "input"))
      (node (ref "USB3") (pin "B5") (pinfunction "CC2_B5") (pintype "unspecified"))
    )
    (net (code "73") (name "unconnected-(LED7-DO-Pad1)") (class "Default")
      (node (ref "LED7") (pin "1") (pinfunction "DO_1") (pintype "unspecified+no_connect"))
    )
    (net (code "74") (name "unconnected-(SCREW1-Pad1)") (class "Default")
      (node (ref "SCREW1") (pin "1") (pinfunction "1_1") (pintype "input+no_connect"))
    )
    (net (code "75") (name "unconnected-(SCREW2-Pad1)") (class "Default")
      (node (ref "SCREW2") (pin "1") (pinfunction "1_1") (pintype "input+no_connect"))
    )
    (net (code "76") (name "unconnected-(SCREW3-Pad1)") (class "Default")
      (node (ref "SCREW3") (pin "1") (pinfunction "1_1") (pintype "input+no_connect"))
    )
    (net (code "77") (name "unconnected-(SCREW4-Pad1)") (class "Default")
      (node (ref "SCREW4") (pin "1") (pinfunction "1_1") (pintype "input+no_connect"))
    )
    (net (code "78") (name "unconnected-(U8A-PA0-WKUP(PA0)-Pad14)") (class "Default")
      (node (ref "U8") (pin "14") (pinfunction "PA0-WKUP(PA0)_14") (pintype "bidirectional+no_connect"))
    )
    (net (code "79") (name "unconnected-(U8A-PA1-Pad15)") (class "Default")
      (node (ref "U8") (pin "15") (pinfunction "PA1_15") (pintype "bidirectional+no_connect"))
    )
    (net (code "80") (name "unconnected-(U50-RESV-Pad2)") (class "Default")
      (node (ref "U50") (pin "2") (pinfunction "RESV_2") (pintype "unspecified+no_connect"))
    )
    (net (code "81") (name "unconnected-(U50-RESV-Pad3)") (class "Default")
      (node (ref "U50") (pin "3") (pinfunction "RESV_3") (pintype "unspecified+no_connect"))
    )
    (net (code "82") (name "unconnected-(U50-RESV-Pad10)") (class "Default")
      (node (ref "U50") (pin "10") (pinfunction "RESV_10") (pintype "unspecified+no_connect"))
    )
    (net (code "83") (name "unconnected-(U52-PG-Pad2)") (class "Default")
      (node (ref "U52") (pin "2") (pinfunction "PG_2") (pintype "unspecified+no_connect"))
    )
    (net (code "84") (name "unconnected-(U58-NC-Pad4)") (class "Default")
      (node (ref "U58") (pin "4") (pinfunction "NC_4") (pintype "unspecified+no_connect"))
    )
    (net (code "85") (name "unconnected-(USB3-SUB1-PadA8)") (class "Default")
      (node (ref "USB3") (pin "A8") (pinfunction "SUB1_A8") (pintype "unspecified+no_connect"))
    )
    (net (code "86") (name "unconnected-(USB3-SUB2-PadB8)") (class "Default")
      (node (ref "USB3") (pin "B8") (pinfunction "SUB2_B8") (pintype "unspecified+no_connect"))
    )
  )
)
